# MCU.net
KiCad netlist of a schematic drawn in Altium Designer
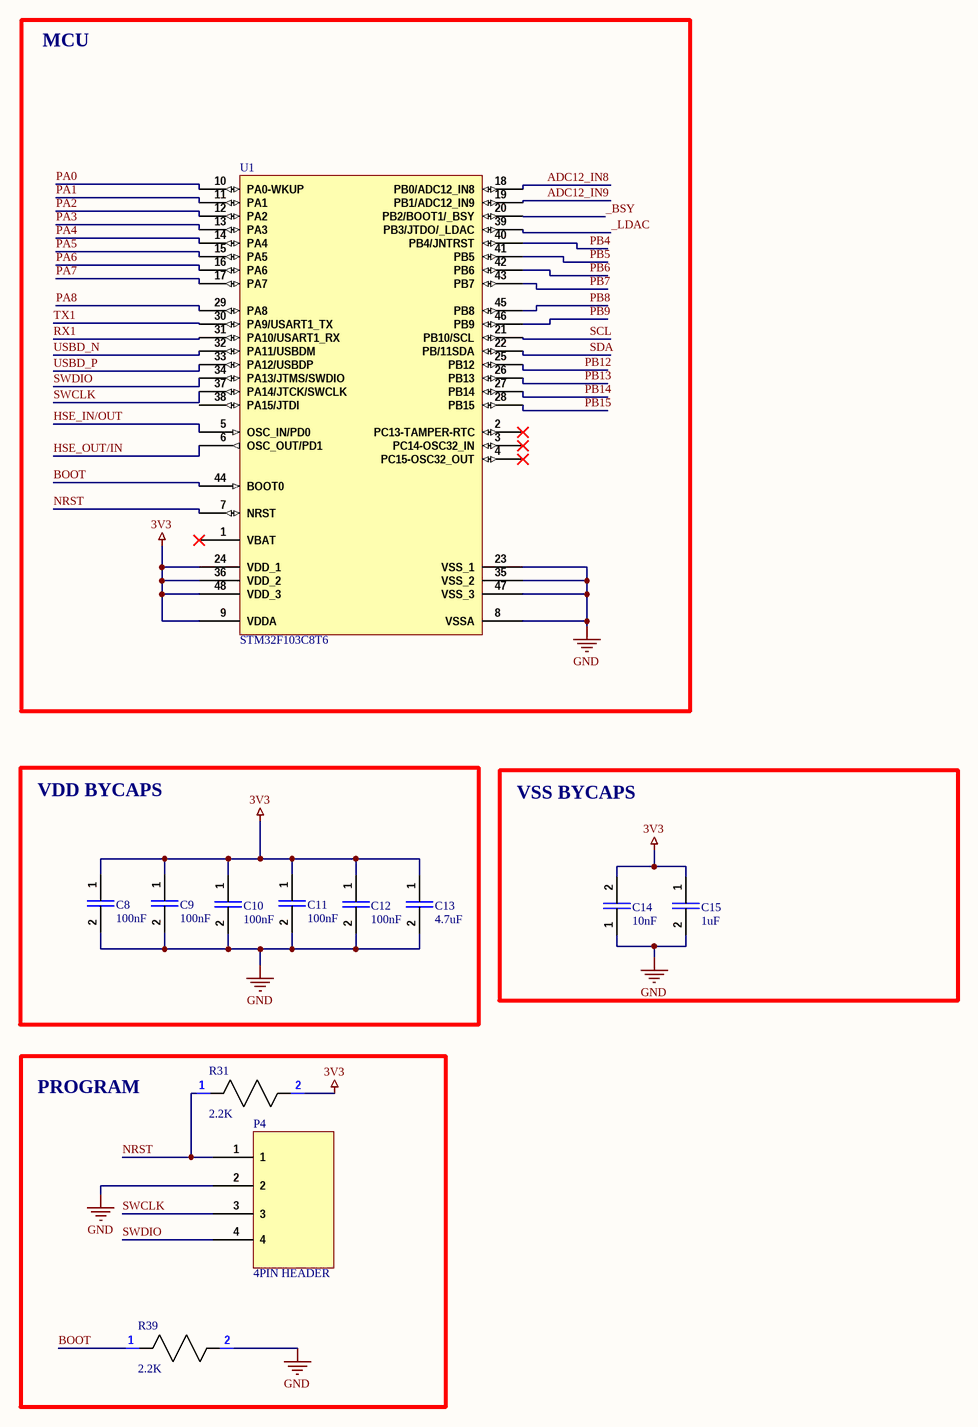
[diagram p0: MCU.SchDoc]

(export (version "E")
  (design (tool "Eeschema 10.0.6"))
  (components
    (comp (ref "C8")
      (value "100nF")
      (footprint "0603 Cap")
      (description "SMD 0603 (ceramic) capacitor")
      (fields
        (field (name "MANUFACTURER") "Murata")
        (field (name "MANUFACTURER PART NUMBER") "GRM21BR71C225KA12L")
      )
      (libsource (lib "Lib") (part "0603 Cap"))
    )
    (comp (ref "C9")
      (value "100nF")
      (footprint "0603 Cap")
      (description "SMD 0603 (ceramic) capacitor")
      (fields
        (field (name "MANUFACTURER") "Murata")
        (field (name "MANUFACTURER PART NUMBER") "GRM21BR71C225KA12L")
      )
      (libsource (lib "Lib") (part "0603 Cap"))
    )
    (comp (ref "C10")
      (value "100nF")
      (footprint "0603 Cap")
      (description "SMD 0603 (ceramic) capacitor")
      (fields
        (field (name "MANUFACTURER") "Murata")
        (field (name "MANUFACTURER PART NUMBER") "GRM21BR71C225KA12L")
      )
      (libsource (lib "Lib") (part "0603 Cap"))
    )
    (comp (ref "C11")
      (value "100nF")
      (footprint "0603 Cap")
      (description "SMD 0603 (ceramic) capacitor")
      (fields
        (field (name "MANUFACTURER") "Murata")
        (field (name "MANUFACTURER PART NUMBER") "GRM21BR71C225KA12L")
      )
      (libsource (lib "Lib") (part "0603 Cap"))
    )
    (comp (ref "C12")
      (value "100nF")
      (footprint "0603 Cap")
      (description "SMD 0603 (ceramic) capacitor")
      (fields
        (field (name "MANUFACTURER") "Murata")
        (field (name "MANUFACTURER PART NUMBER") "GRM21BR71C225KA12L")
      )
      (libsource (lib "Lib") (part "0603 Cap"))
    )
    (comp (ref "C13")
      (value "4.7uF")
      (footprint "0603 Cap")
      (description "SMD 0603 (ceramic) capacitor")
      (fields
        (field (name "MANUFACTURER") "Murata")
        (field (name "MANUFACTURER PART NUMBER") "GRM21BR71C225KA12L")
      )
      (libsource (lib "Lib") (part "0603 Cap"))
    )
    (comp (ref "C14")
      (value "10nF")
      (footprint "0603 Cap")
      (description "SMD 0603 (ceramic) capacitor")
      (fields
        (field (name "MANUFACTURER") "Murata")
        (field (name "MANUFACTURER PART NUMBER") "GRM21BR71C225KA12L")
      )
      (libsource (lib "Lib") (part "0603 Cap"))
    )
    (comp (ref "C15")
      (value "1uF")
      (footprint "0603 Cap")
      (description "SMD 0603 (ceramic) capacitor")
      (fields
        (field (name "MANUFACTURER") "Murata")
        (field (name "MANUFACTURER PART NUMBER") "GRM21BR71C225KA12L")
      )
      (libsource (lib "Lib") (part "0603 Cap"))
    )
    (comp (ref "P4")
      (value "4PIN HEADER")
      (footprint "SM04B-SRSS-TB")
      (libsource (lib "Lib") (part "4X HEADER"))
    )
    (comp (ref "R31")
      (value "2.2K")
      (footprint "0603 RES")
      (description "Can be used for SMD resistors")
      (fields (field (name "Comment") "Resistor"))
      (libsource (lib "Lib") (part "0603 Res"))
    )
    (comp (ref "R39")
      (value "2.2K")
      (footprint "0603 RES")
      (description "Can be used for SMD resistors")
      (fields (field (name "Comment") "Resistor"))
      (libsource (lib "Lib") (part "0603 Res"))
    )
    (comp (ref "U1")
      (value "STM32F103C8T6")
      (footprint "LQFP48_N")
      (description "STM32 ARM-based 32-bit MCU with 64 Kbytes Flash, 48-pin LQFP, Industrial Temperature")
      (fields (field (name "PUBLISHER") "Altium Limited"))
      (libsource (lib "ST Microcontroller 32-Bit STM32") (part "STM32F103C8T6"))
    )
  )
  (nets
    (net (code "1") (name "/ADC12_IN8") (class "Default")
      (node (ref "U1") (pin "18") (pinfunction "PB0/ADC12_IN8_18") (pintype "bidirectional"))
    )
    (net (code "2") (name "/ADC12_IN9") (class "Default")
      (node (ref "U1") (pin "19") (pinfunction "PB1/ADC12_IN9_19") (pintype "bidirectional"))
    )
    (net (code "3") (name "/BOOT") (class "Default")
      (node (ref "R39") (pin "1") (pinfunction "22_1") (pintype "passive"))
      (node (ref "U1") (pin "44") (pinfunction "BOOT0_44") (pintype "input"))
    )
    (net (code "4") (name "/HSE_IN{slash}OUT") (class "Default")
      (node (ref "U1") (pin "5") (pinfunction "OSC_IN/PD0_5") (pintype "input"))
    )
    (net (code "5") (name "/HSE_OUT{slash}IN") (class "Default")
      (node (ref "U1") (pin "6") (pinfunction "OSC_OUT/PD1_6") (pintype "output"))
    )
    (net (code "6") (name "/NRST") (class "Default")
      (node (ref "P4") (pin "1") (pinfunction "1_1") (pintype "passive"))
      (node (ref "R31") (pin "1") (pinfunction "22_1") (pintype "passive"))
      (node (ref "U1") (pin "7") (pinfunction "NRST_7") (pintype "bidirectional"))
    )
    (net (code "7") (name "/PA0") (class "Default")
      (node (ref "U1") (pin "10") (pinfunction "PA0-WKUP_10") (pintype "bidirectional"))
    )
    (net (code "8") (name "/PA1") (class "Default")
      (node (ref "U1") (pin "11") (pinfunction "PA1_11") (pintype "bidirectional"))
    )
    (net (code "9") (name "/PA2") (class "Default")
      (node (ref "U1") (pin "12") (pinfunction "PA2_12") (pintype "bidirectional"))
    )
    (net (code "10") (name "/PA3") (class "Default")
      (node (ref "U1") (pin "13") (pinfunction "PA3_13") (pintype "bidirectional"))
    )
    (net (code "11") (name "/PA4") (class "Default")
      (node (ref "U1") (pin "14") (pinfunction "PA4_14") (pintype "bidirectional"))
    )
    (net (code "12") (name "/PA5") (class "Default")
      (node (ref "U1") (pin "15") (pinfunction "PA5_15") (pintype "bidirectional"))
    )
    (net (code "13") (name "/PA6") (class "Default")
      (node (ref "U1") (pin "16") (pinfunction "PA6_16") (pintype "bidirectional"))
    )
    (net (code "14") (name "/PA7") (class "Default")
      (node (ref "U1") (pin "17") (pinfunction "PA7_17") (pintype "bidirectional"))
    )
    (net (code "15") (name "/PA8") (class "Default")
      (node (ref "U1") (pin "29") (pinfunction "PA8_29") (pintype "bidirectional"))
    )
    (net (code "16") (name "/PB4") (class "Default")
      (node (ref "U1") (pin "40") (pinfunction "PB4/JNTRST_40") (pintype "bidirectional"))
    )
    (net (code "17") (name "/PB5") (class "Default")
      (node (ref "U1") (pin "41") (pinfunction "PB5_41") (pintype "bidirectional"))
    )
    (net (code "18") (name "/PB6") (class "Default")
      (node (ref "U1") (pin "42") (pinfunction "PB6_42") (pintype "bidirectional"))
    )
    (net (code "19") (name "/PB7") (class "Default")
      (node (ref "U1") (pin "43") (pinfunction "PB7_43") (pintype "bidirectional"))
    )
    (net (code "20") (name "/PB8") (class "Default")
      (node (ref "U1") (pin "45") (pinfunction "PB8_45") (pintype "bidirectional"))
    )
    (net (code "21") (name "/PB9") (class "Default")
      (node (ref "U1") (pin "46") (pinfunction "PB9_46") (pintype "bidirectional"))
    )
    (net (code "22") (name "/PB12") (class "Default")
      (node (ref "U1") (pin "25") (pinfunction "PB12_25") (pintype "bidirectional"))
    )
    (net (code "23") (name "/PB13") (class "Default")
      (node (ref "U1") (pin "26") (pinfunction "PB13_26") (pintype "bidirectional"))
    )
    (net (code "24") (name "/PB14") (class "Default")
      (node (ref "U1") (pin "27") (pinfunction "PB14_27") (pintype "bidirectional"))
    )
    (net (code "25") (name "/PB15") (class "Default")
      (node (ref "U1") (pin "28") (pinfunction "PB15_28") (pintype "bidirectional"))
    )
    (net (code "26") (name "/RX1") (class "Default")
      (node (ref "U1") (pin "31") (pinfunction "PA10/USART1_RX_31") (pintype "bidirectional"))
    )
    (net (code "27") (name "/SCL") (class "Default")
      (node (ref "U1") (pin "21") (pinfunction "PB10/SCL_21") (pintype "bidirectional"))
    )
    (net (code "28") (name "/SDA") (class "Default")
      (node (ref "U1") (pin "22") (pinfunction "PB/11SDA_22") (pintype "bidirectional"))
    )
    (net (code "29") (name "/SWCLK") (class "Default")
      (node (ref "P4") (pin "3") (pinfunction "3_3") (pintype "passive"))
      (node (ref "U1") (pin "37") (pinfunction "PA14/JTCK/SWCLK_37") (pintype "bidirectional"))
    )
    (net (code "30") (name "/SWDIO") (class "Default")
      (node (ref "P4") (pin "4") (pinfunction "4_4") (pintype "passive"))
      (node (ref "U1") (pin "34") (pinfunction "PA13/JTMS/SWDIO_34") (pintype "bidirectional"))
    )
    (net (code "31") (name "/TX1") (class "Default")
      (node (ref "U1") (pin "30") (pinfunction "PA9/USART1_TX_30") (pintype "bidirectional"))
    )
    (net (code "32") (name "/USBD_N") (class "Default")
      (node (ref "U1") (pin "32") (pinfunction "PA11/USBDM_32") (pintype "bidirectional"))
    )
    (net (code "33") (name "/USBD_P") (class "Default")
      (node (ref "U1") (pin "33") (pinfunction "PA12/USBDP_33") (pintype "bidirectional"))
    )
    (net (code "34") (name "/_BSY") (class "Default")
      (node (ref "U1") (pin "20") (pinfunction "PB2/BOOT1/_BSY_20") (pintype "bidirectional"))
    )
    (net (code "35") (name "/_LDAC") (class "Default")
      (node (ref "U1") (pin "39") (pinfunction "PB3/JTDO/_LDAC_39") (pintype "bidirectional"))
    )
    (net (code "36") (name "3V3") (class "Default")
      (node (ref "C10") (pin "1") (pinfunction "11_1") (pintype "passive"))
      (node (ref "C11") (pin "1") (pinfunction "11_1") (pintype "passive"))
      (node (ref "C12") (pin "1") (pinfunction "11_1") (pintype "passive"))
      (node (ref "C13") (pin "1") (pinfunction "11_1") (pintype "passive"))
      (node (ref "C14") (pin "2") (pinfunction "12_2") (pintype "passive"))
      (node (ref "C15") (pin "1") (pinfunction "11_1") (pintype "passive"))
      (node (ref "C8") (pin "1") (pinfunction "11_1") (pintype "passive"))
      (node (ref "C9") (pin "1") (pinfunction "11_1") (pintype "passive"))
      (node (ref "R31") (pin "2") (pinfunction "21_2") (pintype "passive"))
      (node (ref "U1") (pin "24") (pinfunction "VDD_1_24") (pintype "power_in"))
      (node (ref "U1") (pin "36") (pinfunction "VDD_2_36") (pintype "power_in"))
      (node (ref "U1") (pin "48") (pinfunction "VDD_3_48") (pintype "power_in"))
      (node (ref "U1") (pin "9") (pinfunction "VDDA_9") (pintype "power_in"))
    )
    (net (code "37") (name "GND") (class "Default")
      (node (ref "C10") (pin "2") (pinfunction "12_2") (pintype "passive"))
      (node (ref "C11") (pin "2") (pinfunction "12_2") (pintype "passive"))
      (node (ref "C12") (pin "2") (pinfunction "12_2") (pintype "passive"))
      (node (ref "C13") (pin "2") (pinfunction "12_2") (pintype "passive"))
      (node (ref "C14") (pin "1") (pinfunction "11_1") (pintype "passive"))
      (node (ref "C15") (pin "2") (pinfunction "12_2") (pintype "passive"))
      (node (ref "C8") (pin "2") (pinfunction "12_2") (pintype "passive"))
      (node (ref "C9") (pin "2") (pinfunction "12_2") (pintype "passive"))
      (node (ref "P4") (pin "2") (pinfunction "2_2") (pintype "passive"))
      (node (ref "R39") (pin "2") (pinfunction "21_2") (pintype "passive"))
      (node (ref "U1") (pin "23") (pinfunction "VSS_1_23") (pintype "power_in"))
      (node (ref "U1") (pin "35") (pinfunction "VSS_2_35") (pintype "power_in"))
      (node (ref "U1") (pin "47") (pinfunction "VSS_3_47") (pintype "power_in"))
      (node (ref "U1") (pin "8") (pinfunction "VSSA_8") (pintype "power_in"))
    )
    (net (code "38") (name "unconnected-(U1-PA15{slash}JTDI-Pad38)") (class "Default")
      (node (ref "U1") (pin "38") (pinfunction "PA15/JTDI_38") (pintype "bidirectional"))
    )
    (net (code "39") (name "unconnected-(U1-PC13-TAMPER-RTC-Pad2)") (class "Default")
      (node (ref "U1") (pin "2") (pinfunction "PC13-TAMPER-RTC_2") (pintype "bidirectional+no_connect"))
    )
    (net (code "40") (name "unconnected-(U1-PC14-OSC32_IN-Pad3)") (class "Default")
      (node (ref "U1") (pin "3") (pinfunction "PC14-OSC32_IN_3") (pintype "bidirectional+no_connect"))
    )
    (net (code "41") (name "unconnected-(U1-PC15-OSC32_OUT-Pad4)") (class "Default")
      (node (ref "U1") (pin "4") (pinfunction "PC15-OSC32_OUT_4") (pintype "bidirectional+no_connect"))
    )
    (net (code "42") (name "unconnected-(U1-VBAT-Pad1)") (class "Default")
      (node (ref "U1") (pin "1") (pinfunction "VBAT_1") (pintype "power_in+no_connect"))
    )
  )
)
